# Digital_Isolator.net
KiCad netlist of a schematic drawn in Altium Designer
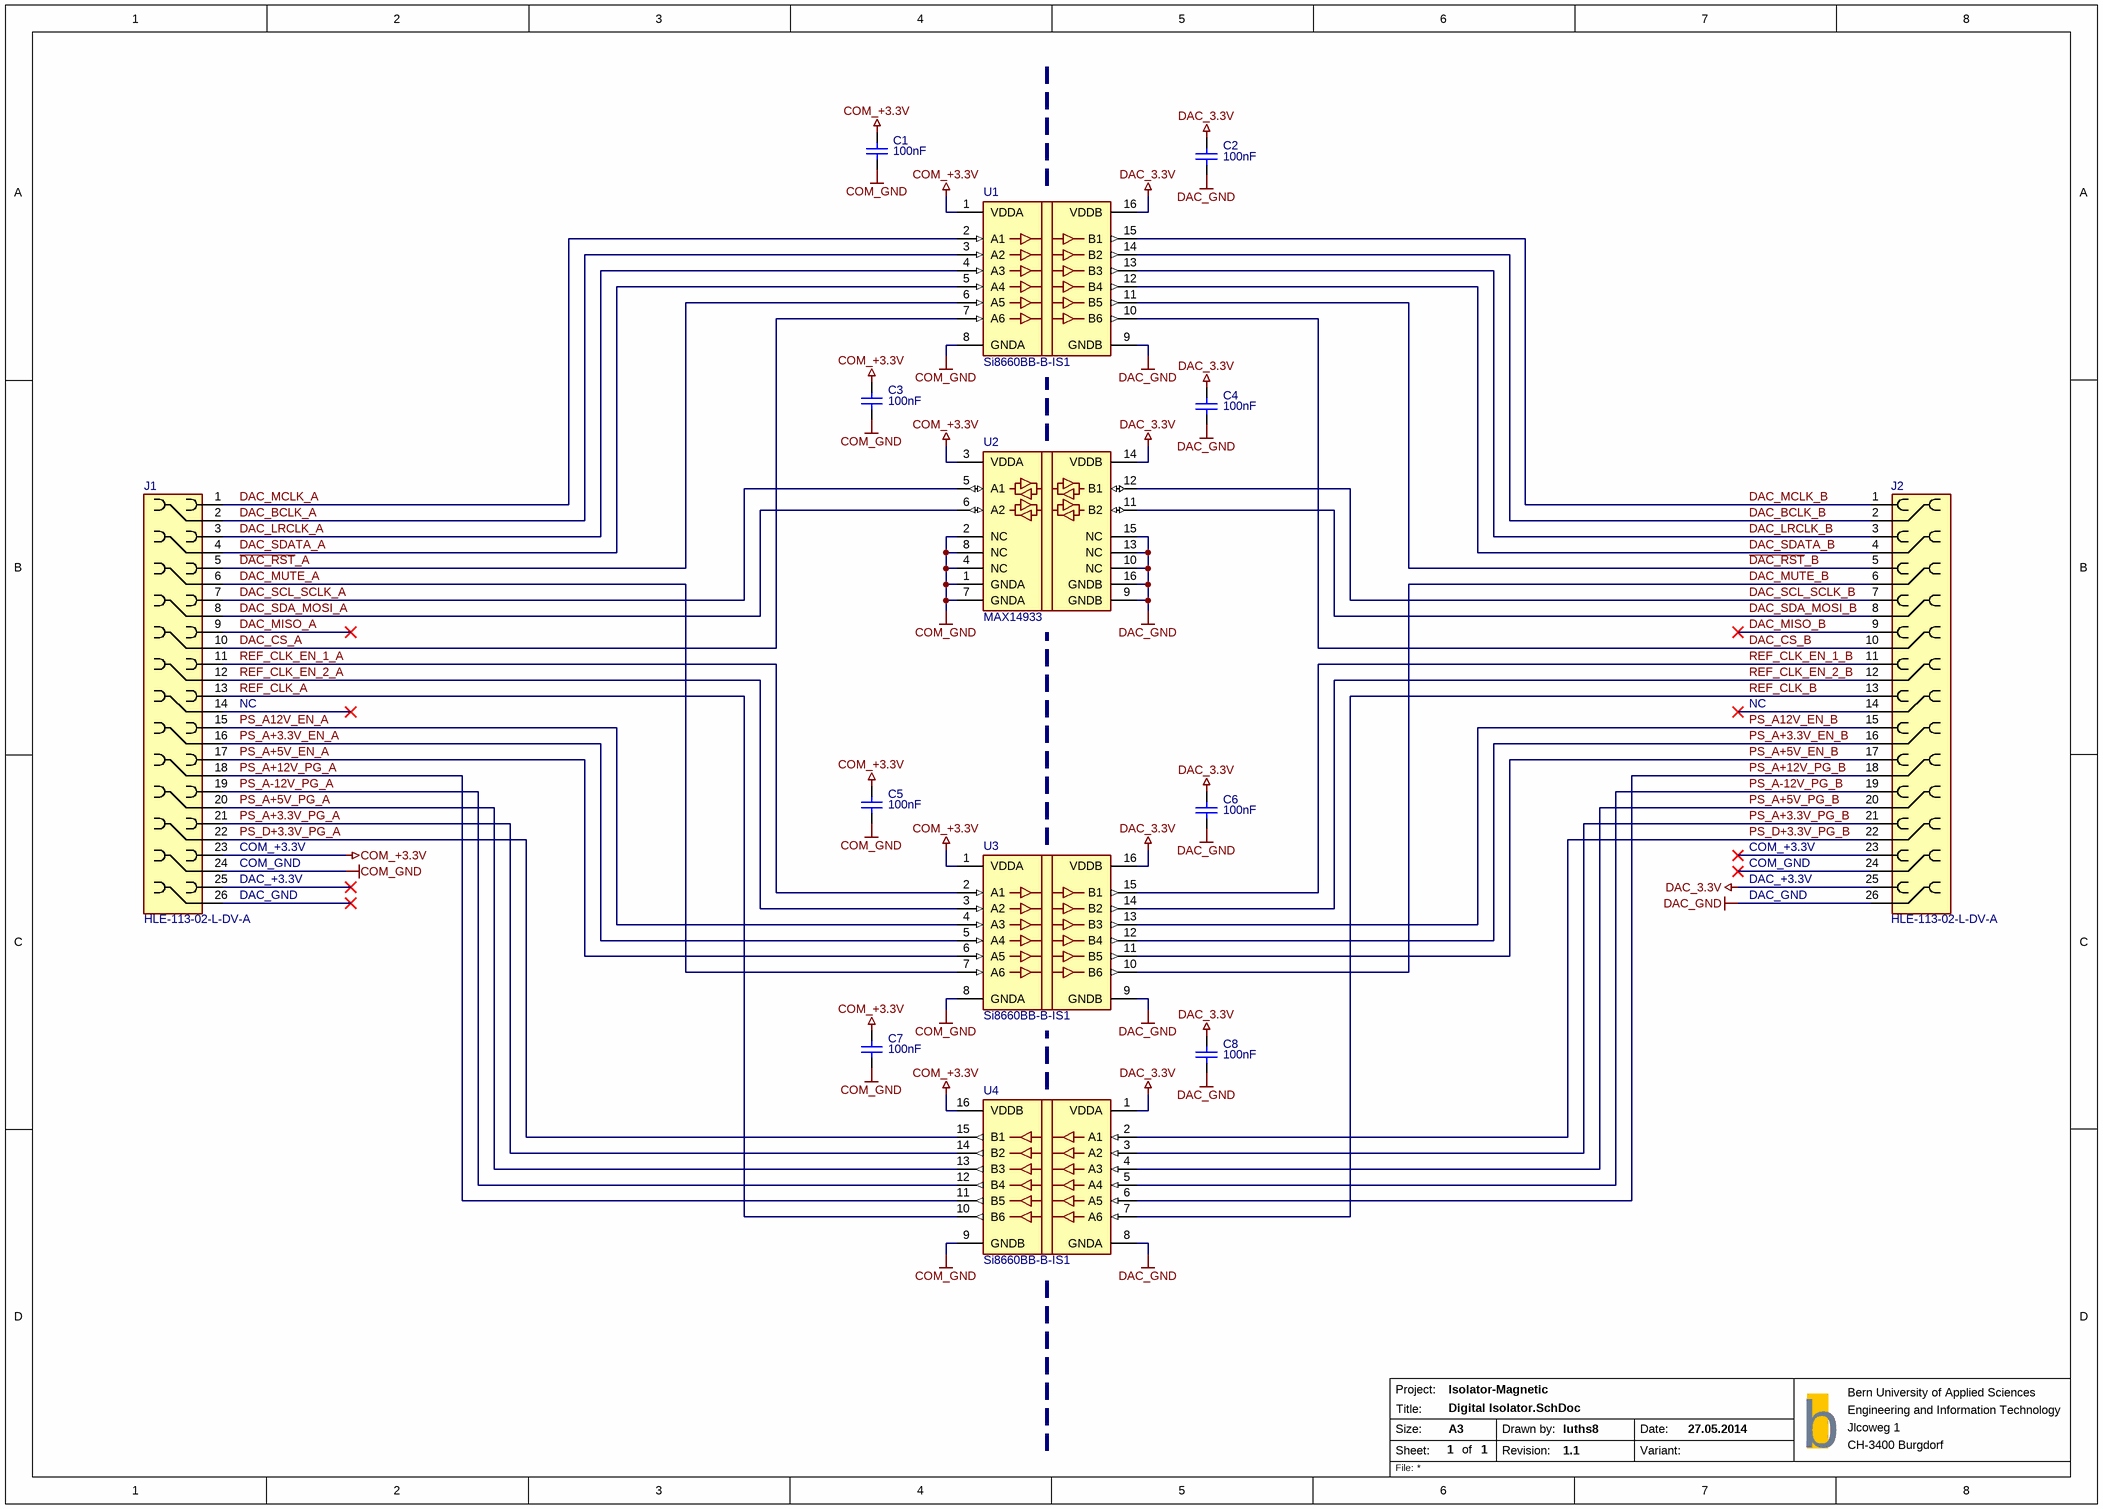
[diagram p0: Digital Isolator.SchDoc]

(export (version "E")
  (design (tool "Eeschema 10.0.6"))
  (components
    (comp (ref "C1")
      (value "100nF")
      (footprint "SMD0603CAP")
      (description "Ceramic Capacitor")
      (libsource (lib "Audio-Streamer") (part "Capacitor Ceramic"))
    )
    (comp (ref "C2")
      (value "100nF")
      (footprint "SMD0603CAP")
      (description "Ceramic Capacitor")
      (libsource (lib "Audio-Streamer") (part "Capacitor Ceramic"))
    )
    (comp (ref "C3")
      (value "100nF")
      (footprint "SMD0603CAP")
      (description "Ceramic Capacitor")
      (libsource (lib "Audio-Streamer") (part "Capacitor Ceramic"))
    )
    (comp (ref "C4")
      (value "100nF")
      (footprint "SMD0603CAP")
      (description "Ceramic Capacitor")
      (libsource (lib "Audio-Streamer") (part "Capacitor Ceramic"))
    )
    (comp (ref "C5")
      (value "100nF")
      (footprint "SMD0603CAP")
      (description "Ceramic Capacitor")
      (libsource (lib "Audio-Streamer") (part "Capacitor Ceramic"))
    )
    (comp (ref "C6")
      (value "100nF")
      (footprint "SMD0603CAP")
      (description "Ceramic Capacitor")
      (libsource (lib "Audio-Streamer") (part "Capacitor Ceramic"))
    )
    (comp (ref "C7")
      (value "100nF")
      (footprint "SMD0603CAP")
      (description "Ceramic Capacitor")
      (libsource (lib "Audio-Streamer") (part "Capacitor Ceramic"))
    )
    (comp (ref "C8")
      (value "100nF")
      (footprint "SMD0603CAP")
      (description "Ceramic Capacitor")
      (libsource (lib "Audio-Streamer") (part "Capacitor Ceramic"))
    )
    (comp (ref "J1")
      (value "HLE-113-02-L-DV-A")
      (footprint "HLE-113-02-XXX-DV-A")
      (description "Receptacle 13x2P")
      (libsource (lib "Audio-Streamer") (part "Receptacle 13x2P"))
    )
    (comp (ref "J2")
      (value "HLE-113-02-L-DV-A")
      (footprint "HLE-113-02-XXX-DV-A")
      (description "Receptacle 13x2P")
      (libsource (lib "Audio-Streamer") (part "Receptacle 13x2P"))
    )
    (comp (ref "U1")
      (value "Si8660BB-B-IS1")
      (footprint "SOIC16")
      (description "Unidirectional digital isolator")
      (libsource (lib "Audio-Streamer") (part "Si8660BB-B-IS1"))
    )
    (comp (ref "U2")
      (value "MAX14933")
      (footprint "SOIC16")
      (description "Bidirectional digital isolator")
      (fields (field (name "MANUFACTURER PART NO.") "MAX14933ASE+"))
      (libsource (lib "Audio-Streamer") (part "MAX14933"))
    )
    (comp (ref "U3")
      (value "Si8660BB-B-IS1")
      (footprint "SOIC16")
      (description "Unidirectional digital isolator")
      (libsource (lib "Audio-Streamer") (part "Si8660BB-B-IS1"))
    )
    (comp (ref "U4")
      (value "Si8660BB-B-IS1")
      (footprint "SOIC16")
      (description "Unidirectional digital isolator")
      (libsource (lib "") (part "Si8660BB-B-IS1_1"))
    )
  )
  (nets
    (net (code "1") (name "/DAC_BCLK_A") (class "Default")
      (node (ref "J1") (pin "2") (pinfunction "2_2") (pintype "passive"))
      (node (ref "U1") (pin "3") (pinfunction "A2_3") (pintype "input"))
    )
    (net (code "2") (name "/DAC_BCLK_B") (class "Default")
      (node (ref "J2") (pin "2") (pinfunction "2_2") (pintype "passive"))
      (node (ref "U1") (pin "14") (pinfunction "B2_14") (pintype "output"))
    )
    (net (code "3") (name "/DAC_CS_A") (class "Default")
      (node (ref "J1") (pin "10") (pinfunction "10_10") (pintype "passive"))
      (node (ref "U1") (pin "7") (pinfunction "A6_7") (pintype "input"))
    )
    (net (code "4") (name "/DAC_CS_B") (class "Default")
      (node (ref "J2") (pin "10") (pinfunction "10_10") (pintype "passive"))
      (node (ref "U1") (pin "10") (pinfunction "B6_10") (pintype "output"))
    )
    (net (code "5") (name "/DAC_LRCLK_A") (class "Default")
      (node (ref "J1") (pin "3") (pinfunction "3_3") (pintype "passive"))
      (node (ref "U1") (pin "4") (pinfunction "A3_4") (pintype "input"))
    )
    (net (code "6") (name "/DAC_LRCLK_B") (class "Default")
      (node (ref "J2") (pin "3") (pinfunction "3_3") (pintype "passive"))
      (node (ref "U1") (pin "13") (pinfunction "B3_13") (pintype "output"))
    )
    (net (code "7") (name "/DAC_MCLK_A") (class "Default")
      (node (ref "J1") (pin "1") (pinfunction "1_1") (pintype "passive"))
      (node (ref "U1") (pin "2") (pinfunction "A1_2") (pintype "input"))
    )
    (net (code "8") (name "/DAC_MCLK_B") (class "Default")
      (node (ref "J2") (pin "1") (pinfunction "1_1") (pintype "passive"))
      (node (ref "U1") (pin "15") (pinfunction "B1_15") (pintype "output"))
    )
    (net (code "9") (name "/DAC_MISO_A") (class "Default")
      (node (ref "J1") (pin "9") (pinfunction "9_9") (pintype "passive+no_connect"))
    )
    (net (code "10") (name "/DAC_MISO_B") (class "Default")
      (node (ref "J2") (pin "9") (pinfunction "9_9") (pintype "passive+no_connect"))
    )
    (net (code "11") (name "/DAC_MUTE_A") (class "Default")
      (node (ref "J1") (pin "6") (pinfunction "6_6") (pintype "passive"))
      (node (ref "U3") (pin "7") (pinfunction "A6_7") (pintype "input"))
    )
    (net (code "12") (name "/DAC_MUTE_B") (class "Default")
      (node (ref "J2") (pin "6") (pinfunction "6_6") (pintype "passive"))
      (node (ref "U3") (pin "10") (pinfunction "B6_10") (pintype "output"))
    )
    (net (code "13") (name "/DAC_SCL_SCLK_A") (class "Default")
      (node (ref "J1") (pin "7") (pinfunction "7_7") (pintype "passive"))
      (node (ref "U2") (pin "5") (pinfunction "A1_5") (pintype "bidirectional"))
    )
    (net (code "14") (name "/DAC_SCL_SCLK_B") (class "Default")
      (node (ref "J2") (pin "7") (pinfunction "7_7") (pintype "passive"))
      (node (ref "U2") (pin "12") (pinfunction "B1_12") (pintype "bidirectional"))
    )
    (net (code "15") (name "/DAC_SDATA_A") (class "Default")
      (node (ref "J1") (pin "4") (pinfunction "4_4") (pintype "passive"))
      (node (ref "U1") (pin "5") (pinfunction "A4_5") (pintype "input"))
    )
    (net (code "16") (name "/DAC_SDATA_B") (class "Default")
      (node (ref "J2") (pin "4") (pinfunction "4_4") (pintype "passive"))
      (node (ref "U1") (pin "12") (pinfunction "B4_12") (pintype "output"))
    )
    (net (code "17") (name "/DAC_SDA_MOSI_A") (class "Default")
      (node (ref "J1") (pin "8") (pinfunction "8_8") (pintype "passive"))
      (node (ref "U2") (pin "6") (pinfunction "A2_6") (pintype "bidirectional"))
    )
    (net (code "18") (name "/DAC_SDA_MOSI_B") (class "Default")
      (node (ref "J2") (pin "8") (pinfunction "8_8") (pintype "passive"))
      (node (ref "U2") (pin "11") (pinfunction "B2_11") (pintype "bidirectional"))
    )
    (net (code "19") (name "/PS_A+3.3V_EN_A") (class "Default")
      (node (ref "J1") (pin "16") (pinfunction "16_16") (pintype "passive"))
      (node (ref "U3") (pin "5") (pinfunction "A4_5") (pintype "input"))
    )
    (net (code "20") (name "/PS_A+3.3V_EN_B") (class "Default")
      (node (ref "J2") (pin "16") (pinfunction "16_16") (pintype "passive"))
      (node (ref "U3") (pin "12") (pinfunction "B4_12") (pintype "output"))
    )
    (net (code "21") (name "/PS_A+3.3V_PG_A") (class "Default")
      (node (ref "J1") (pin "21") (pinfunction "21_21") (pintype "passive"))
      (node (ref "U4") (pin "14") (pinfunction "B2_14") (pintype "output"))
    )
    (net (code "22") (name "/PS_A+3.3V_PG_B") (class "Default")
      (node (ref "J2") (pin "21") (pinfunction "21_21") (pintype "passive"))
      (node (ref "U4") (pin "3") (pinfunction "A2_3") (pintype "input"))
    )
    (net (code "23") (name "/PS_A+5V_EN_A") (class "Default")
      (node (ref "J1") (pin "17") (pinfunction "17_17") (pintype "passive"))
      (node (ref "U3") (pin "6") (pinfunction "A5_6") (pintype "input"))
    )
    (net (code "24") (name "/PS_A+5V_EN_B") (class "Default")
      (node (ref "J2") (pin "17") (pinfunction "17_17") (pintype "passive"))
      (node (ref "U3") (pin "11") (pinfunction "B5_11") (pintype "output"))
    )
    (net (code "25") (name "/PS_A+5V_PG_A") (class "Default")
      (node (ref "J1") (pin "20") (pinfunction "20_20") (pintype "passive"))
      (node (ref "U4") (pin "13") (pinfunction "B3_13") (pintype "output"))
    )
    (net (code "26") (name "/PS_A+5V_PG_B") (class "Default")
      (node (ref "J2") (pin "20") (pinfunction "20_20") (pintype "passive"))
      (node (ref "U4") (pin "4") (pinfunction "A3_4") (pintype "input"))
    )
    (net (code "27") (name "/PS_A+12V_PG_A") (class "Default")
      (node (ref "J1") (pin "18") (pinfunction "18_18") (pintype "passive"))
      (node (ref "U4") (pin "11") (pinfunction "B5_11") (pintype "output"))
    )
    (net (code "28") (name "/PS_A+12V_PG_B") (class "Default")
      (node (ref "J2") (pin "18") (pinfunction "18_18") (pintype "passive"))
      (node (ref "U4") (pin "6") (pinfunction "A5_6") (pintype "input"))
    )
    (net (code "29") (name "/PS_A-12V_PG_A") (class "Default")
      (node (ref "J1") (pin "19") (pinfunction "19_19") (pintype "passive"))
      (node (ref "U4") (pin "12") (pinfunction "B4_12") (pintype "output"))
    )
    (net (code "30") (name "/PS_A-12V_PG_B") (class "Default")
      (node (ref "J2") (pin "19") (pinfunction "19_19") (pintype "passive"))
      (node (ref "U4") (pin "5") (pinfunction "A4_5") (pintype "input"))
    )
    (net (code "31") (name "/PS_A12V_EN_A") (class "Default")
      (node (ref "J1") (pin "15") (pinfunction "15_15") (pintype "passive"))
      (node (ref "U3") (pin "4") (pinfunction "A3_4") (pintype "input"))
    )
    (net (code "32") (name "/PS_A12V_EN_B") (class "Default")
      (node (ref "J2") (pin "15") (pinfunction "15_15") (pintype "passive"))
      (node (ref "U3") (pin "13") (pinfunction "B3_13") (pintype "output"))
    )
    (net (code "33") (name "/PS_D+3.3V_PG_A") (class "Default")
      (node (ref "J1") (pin "22") (pinfunction "22_22") (pintype "passive"))
      (node (ref "U4") (pin "15") (pinfunction "B1_15") (pintype "output"))
    )
    (net (code "34") (name "/PS_D+3.3V_PG_B") (class "Default")
      (node (ref "J2") (pin "22") (pinfunction "22_22") (pintype "passive"))
      (node (ref "U4") (pin "2") (pinfunction "A1_2") (pintype "input"))
    )
    (net (code "35") (name "/REF_CLK_A") (class "Default")
      (node (ref "J1") (pin "13") (pinfunction "13_13") (pintype "passive"))
      (node (ref "U4") (pin "10") (pinfunction "B6_10") (pintype "output"))
    )
    (net (code "36") (name "/REF_CLK_B") (class "Default")
      (node (ref "J2") (pin "13") (pinfunction "13_13") (pintype "passive"))
      (node (ref "U4") (pin "7") (pinfunction "A6_7") (pintype "input"))
    )
    (net (code "37") (name "/REF_CLK_EN_1_A") (class "Default")
      (node (ref "J1") (pin "11") (pinfunction "11_11") (pintype "passive"))
      (node (ref "U3") (pin "2") (pinfunction "A1_2") (pintype "input"))
    )
    (net (code "38") (name "/REF_CLK_EN_1_B") (class "Default")
      (node (ref "J2") (pin "11") (pinfunction "11_11") (pintype "passive"))
      (node (ref "U3") (pin "15") (pinfunction "B1_15") (pintype "output"))
    )
    (net (code "39") (name "/REF_CLK_EN_2_A") (class "Default")
      (node (ref "J1") (pin "12") (pinfunction "12_12") (pintype "passive"))
      (node (ref "U3") (pin "3") (pinfunction "A2_3") (pintype "input"))
    )
    (net (code "40") (name "/REF_CLK_EN_2_B") (class "Default")
      (node (ref "J2") (pin "12") (pinfunction "12_12") (pintype "passive"))
      (node (ref "U3") (pin "14") (pinfunction "B2_14") (pintype "output"))
    )
    (net (code "41") (name "/~{DAC_RST}_A") (class "Default")
      (node (ref "J1") (pin "5") (pinfunction "5_5") (pintype "passive"))
      (node (ref "U1") (pin "6") (pinfunction "A5_6") (pintype "input"))
    )
    (net (code "42") (name "/~{DAC_RST}_B") (class "Default")
      (node (ref "J2") (pin "5") (pinfunction "5_5") (pintype "passive"))
      (node (ref "U1") (pin "11") (pinfunction "B5_11") (pintype "output"))
    )
    (net (code "43") (name "COM_+3.3V") (class "Default")
      (node (ref "C1") (pin "1") (pinfunction "1_1") (pintype "passive"))
      (node (ref "C3") (pin "1") (pinfunction "1_1") (pintype "passive"))
      (node (ref "C5") (pin "1") (pinfunction "1_1") (pintype "passive"))
      (node (ref "C7") (pin "1") (pinfunction "1_1") (pintype "passive"))
      (node (ref "J1") (pin "23") (pinfunction "23_23") (pintype "passive"))
      (node (ref "U1") (pin "1") (pinfunction "VDDA_1") (pintype "power_in"))
      (node (ref "U2") (pin "3") (pinfunction "VDDA_3") (pintype "power_in"))
      (node (ref "U3") (pin "1") (pinfunction "VDDA_1") (pintype "power_in"))
      (node (ref "U4") (pin "16") (pinfunction "VDDB_16") (pintype "power_in"))
    )
    (net (code "44") (name "COM_GND") (class "Default")
      (node (ref "C1") (pin "2") (pinfunction "q_2") (pintype "passive"))
      (node (ref "C3") (pin "2") (pinfunction "q_2") (pintype "passive"))
      (node (ref "C5") (pin "2") (pinfunction "q_2") (pintype "passive"))
      (node (ref "C7") (pin "2") (pinfunction "q_2") (pintype "passive"))
      (node (ref "J1") (pin "24") (pinfunction "24_24") (pintype "passive"))
      (node (ref "U1") (pin "8") (pinfunction "GNDA_8") (pintype "power_in"))
      (node (ref "U2") (pin "1") (pinfunction "GNDA_1") (pintype "power_in"))
      (node (ref "U2") (pin "2") (pinfunction "NC_2") (pintype "passive"))
      (node (ref "U2") (pin "4") (pinfunction "NC_4") (pintype "passive"))
      (node (ref "U2") (pin "7") (pinfunction "GNDA_7") (pintype "power_in"))
      (node (ref "U2") (pin "8") (pinfunction "NC_8") (pintype "passive"))
      (node (ref "U3") (pin "8") (pinfunction "GNDA_8") (pintype "power_in"))
      (node (ref "U4") (pin "9") (pinfunction "GNDB_9") (pintype "power_in"))
    )
    (net (code "45") (name "DAC_3.3V") (class "Default")
      (node (ref "C2") (pin "1") (pinfunction "1_1") (pintype "passive"))
      (node (ref "C4") (pin "1") (pinfunction "1_1") (pintype "passive"))
      (node (ref "C6") (pin "1") (pinfunction "1_1") (pintype "passive"))
      (node (ref "C8") (pin "1") (pinfunction "1_1") (pintype "passive"))
      (node (ref "J2") (pin "25") (pinfunction "25_25") (pintype "passive"))
      (node (ref "U1") (pin "16") (pinfunction "VDDB_16") (pintype "power_in"))
      (node (ref "U2") (pin "14") (pinfunction "VDDB_14") (pintype "power_in"))
      (node (ref "U3") (pin "16") (pinfunction "VDDB_16") (pintype "power_in"))
      (node (ref "U4") (pin "1") (pinfunction "VDDA_1") (pintype "power_in"))
    )
    (net (code "46") (name "DAC_GND") (class "Default")
      (node (ref "C2") (pin "2") (pinfunction "q_2") (pintype "passive"))
      (node (ref "C4") (pin "2") (pinfunction "q_2") (pintype "passive"))
      (node (ref "C6") (pin "2") (pinfunction "q_2") (pintype "passive"))
      (node (ref "C8") (pin "2") (pinfunction "q_2") (pintype "passive"))
      (node (ref "J2") (pin "26") (pinfunction "26_26") (pintype "passive"))
      (node (ref "U1") (pin "9") (pinfunction "GNDB_9") (pintype "power_in"))
      (node (ref "U2") (pin "10") (pinfunction "NC_10") (pintype "passive"))
      (node (ref "U2") (pin "13") (pinfunction "NC_13") (pintype "passive"))
      (node (ref "U2") (pin "15") (pinfunction "NC_15") (pintype "passive"))
      (node (ref "U2") (pin "16") (pinfunction "GNDB_16") (pintype "power_in"))
      (node (ref "U2") (pin "9") (pinfunction "GNDB_9") (pintype "power_in"))
      (node (ref "U3") (pin "9") (pinfunction "GNDB_9") (pintype "power_in"))
      (node (ref "U4") (pin "8") (pinfunction "GNDA_8") (pintype "power_in"))
    )
    (net (code "47") (name "unconnected-(J1-Pad14)") (class "Default")
      (node (ref "J1") (pin "14") (pinfunction "14_14") (pintype "passive+no_connect"))
    )
    (net (code "48") (name "unconnected-(J1-Pad25)") (class "Default")
      (node (ref "J1") (pin "25") (pinfunction "25_25") (pintype "passive+no_connect"))
    )
    (net (code "49") (name "unconnected-(J1-Pad26)") (class "Default")
      (node (ref "J1") (pin "26") (pinfunction "26_26") (pintype "passive+no_connect"))
    )
    (net (code "50") (name "unconnected-(J2-Pad14)") (class "Default")
      (node (ref "J2") (pin "14") (pinfunction "14_14") (pintype "passive+no_connect"))
    )
    (net (code "51") (name "unconnected-(J2-Pad23)") (class "Default")
      (node (ref "J2") (pin "23") (pinfunction "23_23") (pintype "passive+no_connect"))
    )
    (net (code "52") (name "unconnected-(J2-Pad24)") (class "Default")
      (node (ref "J2") (pin "24") (pinfunction "24_24") (pintype "passive+no_connect"))
    )
  )
)
